# OpenBook_Schematic_v39.net
KiCad netlist of a schematic drawn in EAGLE
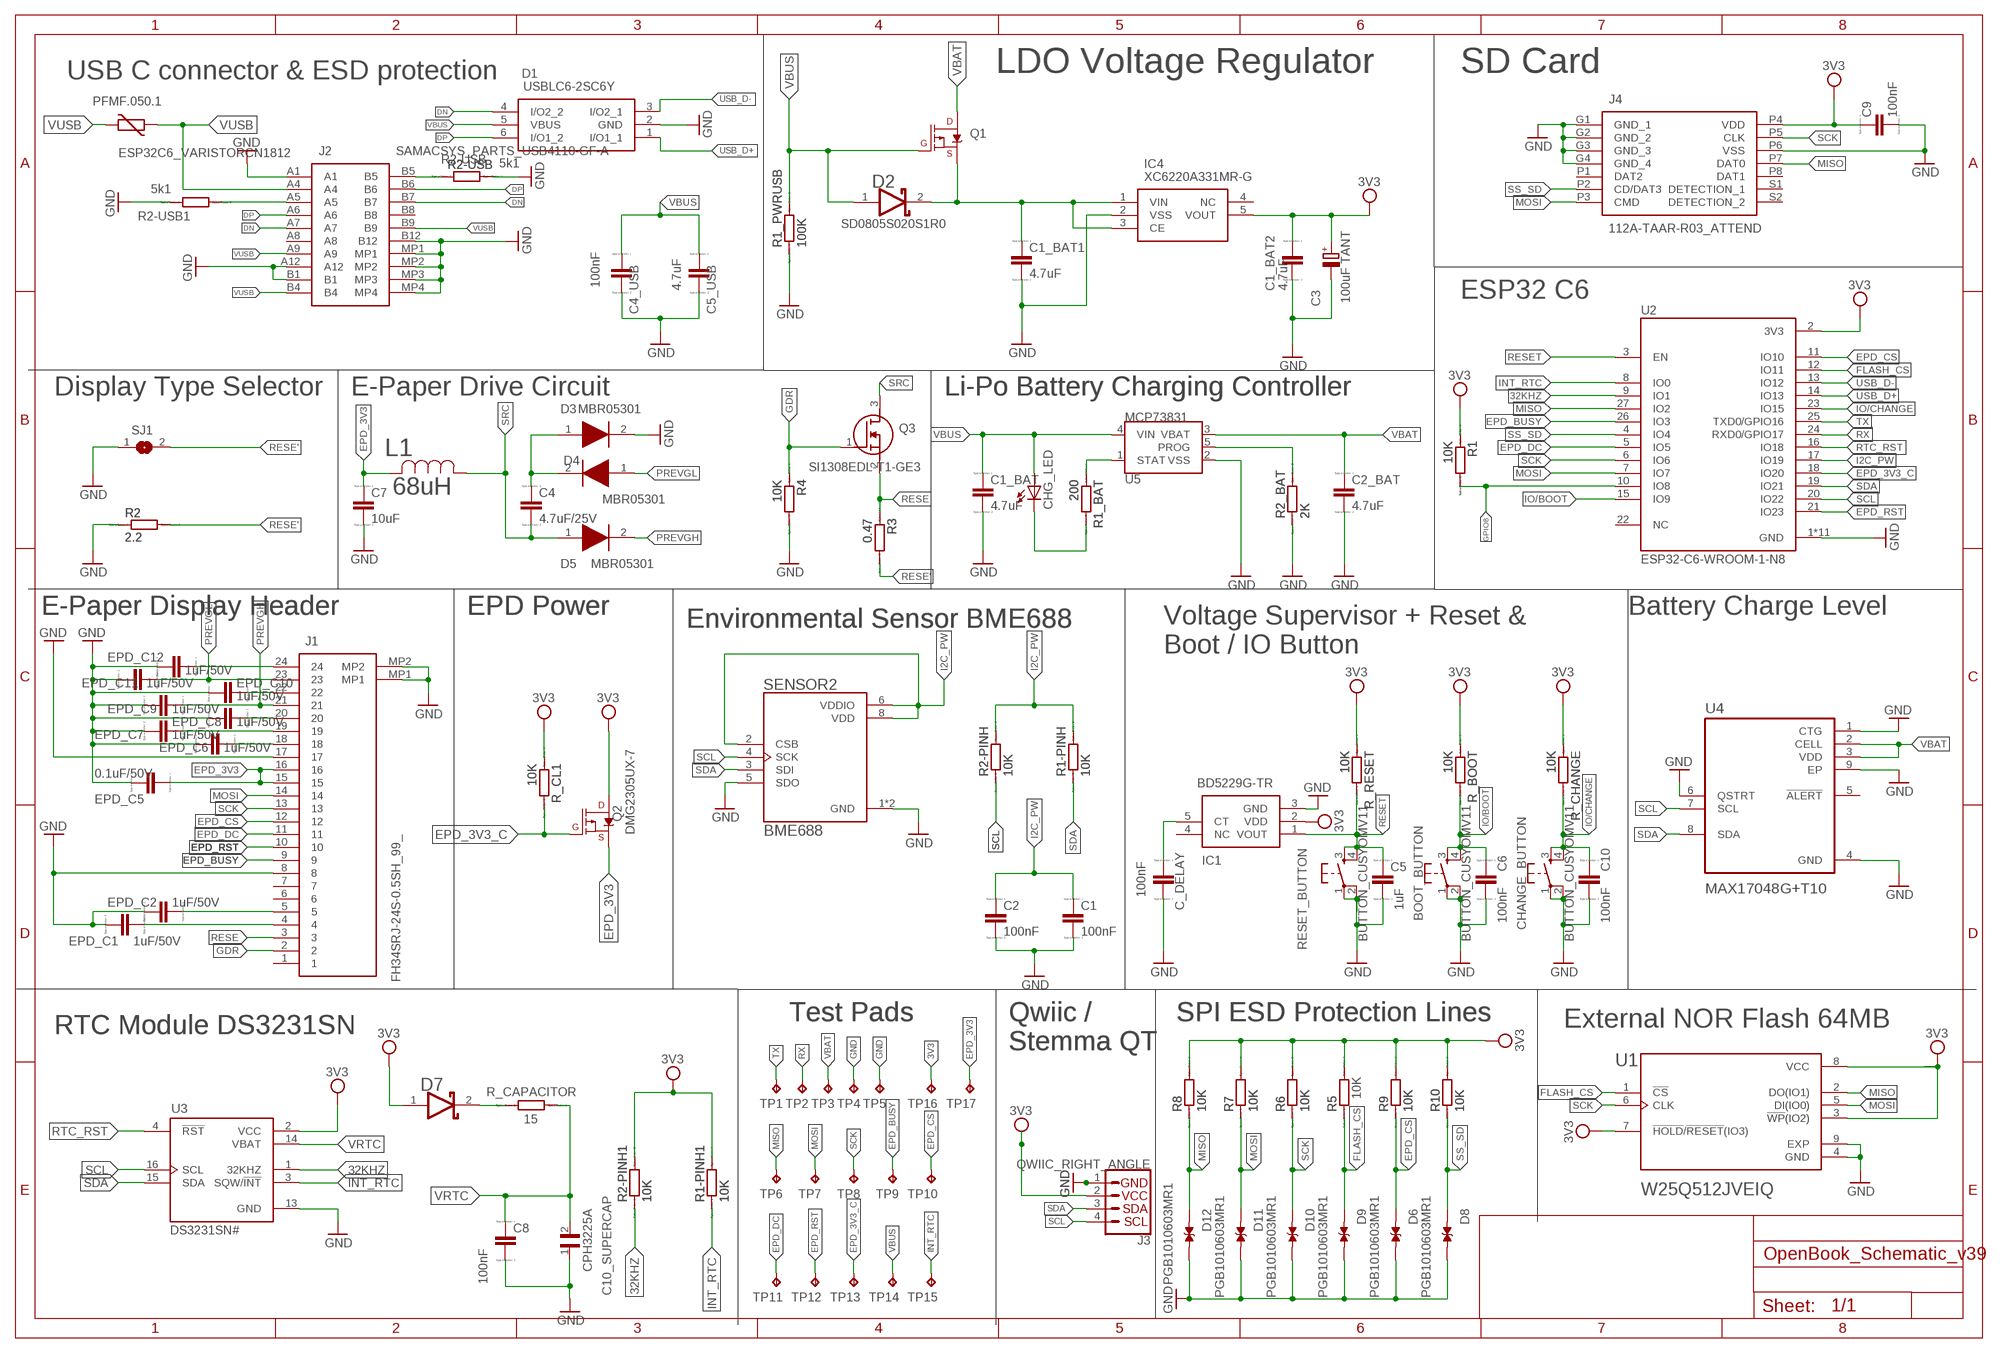
[diagram p0: schematic, sheet 1]

(export (version "E")
  (design (tool "Eeschema 10.0.6"))
  (components
    (comp (ref "BOOT_BUTTON")
      (value "BUTTON_CUSYOMV11")
      (footprint "eagle-import:MYBUTTON")
      (libsource (lib "eagle-import") (part "BUTTON_CUSYOMV11"))
    )
    (comp (ref "C1")
      (value "100nF")
      (footprint "eagle-import:EAGLE-LTSPICE_C0402")
      (libsource (lib "eagle-import") (part "EAGLE-LTSPICE_C"))
    )
    (comp (ref "C1_BAT")
      (value "4.7uF")
      (footprint "eagle-import:EAGLE-LTSPICE_C0402")
      (libsource (lib "eagle-import") (part "EAGLE-LTSPICE_C"))
    )
    (comp (ref "C1_BAT1")
      (value "4.7uF")
      (footprint "eagle-import:EAGLE-LTSPICE_C0402")
      (libsource (lib "eagle-import") (part "EAGLE-LTSPICE_C"))
    )
    (comp (ref "C1_BAT2")
      (value "4.7uF")
      (footprint "eagle-import:EAGLE-LTSPICE_C0402")
      (libsource (lib "eagle-import") (part "EAGLE-LTSPICE_C"))
    )
    (comp (ref "C2")
      (value "100nF")
      (footprint "eagle-import:EAGLE-LTSPICE_C0402")
      (libsource (lib "eagle-import") (part "EAGLE-LTSPICE_C"))
    )
    (comp (ref "C2_BAT")
      (value "4.7uF")
      (footprint "eagle-import:EAGLE-LTSPICE_C0402")
      (libsource (lib "eagle-import") (part "EAGLE-LTSPICE_C"))
    )
    (comp (ref "C3")
      (value "100uF TANT")
      (footprint "eagle-import:RCL_CT3528")
      (libsource (lib "eagle-import") (part "RCL_CPOL-EUCT3528"))
    )
    (comp (ref "C4")
      (value "4.7uF/25V")
      (footprint "eagle-import:EAGLE-LTSPICE_C0402")
      (libsource (lib "eagle-import") (part "EAGLE-LTSPICE_C"))
    )
    (comp (ref "C4_USB")
      (value "100nF")
      (footprint "eagle-import:EAGLE-LTSPICE_C0402")
      (libsource (lib "eagle-import") (part "EAGLE-LTSPICE_C"))
    )
    (comp (ref "C5")
      (value "1uF")
      (footprint "eagle-import:EAGLE-LTSPICE_C0402")
      (libsource (lib "eagle-import") (part "EAGLE-LTSPICE_C"))
    )
    (comp (ref "C5_USB")
      (value "4.7uF")
      (footprint "eagle-import:EAGLE-LTSPICE_C0402")
      (libsource (lib "eagle-import") (part "EAGLE-LTSPICE_C"))
    )
    (comp (ref "C6")
      (value "100nF")
      (footprint "eagle-import:EAGLE-LTSPICE_C0402")
      (libsource (lib "eagle-import") (part "EAGLE-LTSPICE_C"))
    )
    (comp (ref "C7")
      (value "10uF")
      (footprint "eagle-import:EAGLE-LTSPICE_C0402")
      (libsource (lib "eagle-import") (part "EAGLE-LTSPICE_C"))
    )
    (comp (ref "C8")
      (value "100nF")
      (footprint "eagle-import:EAGLE-LTSPICE_C0402")
      (libsource (lib "eagle-import") (part "EAGLE-LTSPICE_C"))
    )
    (comp (ref "C9")
      (value "100nF")
      (footprint "eagle-import:EAGLE-LTSPICE_C0402")
      (libsource (lib "eagle-import") (part "EAGLE-LTSPICE_C"))
    )
    (comp (ref "C10")
      (value "100nF")
      (footprint "eagle-import:EAGLE-LTSPICE_C0402")
      (libsource (lib "eagle-import") (part "EAGLE-LTSPICE_C"))
    )
    (comp (ref "C10_SUPERCAP")
      (value "CPH3225A")
      (footprint "eagle-import:CAPCP3225X100N")
      (fields (field (name "MF") "Seiko Instruments"))
      (libsource (lib "eagle-import") (part "CPH3225A"))
    )
    (comp (ref "CHANGE_BUTTON")
      (value "BUTTON_CUSYOMV11")
      (footprint "eagle-import:MYBUTTON")
      (libsource (lib "eagle-import") (part "BUTTON_CUSYOMV11"))
    )
    (comp (ref "CHG_LED")
      (value "ADAFRUIT_LEDCHIP-LED0603")
      (footprint "eagle-import:ADAFRUIT_CHIP-LED0603")
      (libsource (lib "eagle-import") (part "ADAFRUIT_LEDCHIP-LED0603"))
    )
    (comp (ref "C_DELAY")
      (value "100nF")
      (footprint "eagle-import:EAGLE-LTSPICE_C0402")
      (libsource (lib "eagle-import") (part "EAGLE-LTSPICE_C"))
    )
    (comp (ref "D1")
      (value "USBLC6-2SC6Y")
      (footprint "eagle-import:SOT95P280X145-6N")
      (fields (field (name "MF") "STMicroelectronics"))
      (libsource (lib "eagle-import") (part "USBLC6-2SC6Y"))
    )
    (comp (ref "D2")
      (value "SD0805S020S1R0")
      (footprint "eagle-import:ESP32_WROVER_AVX---SD0805S020S1R0_AVX_SD0805S020S1R0_0")
      (fields (field (name "MINE") "SD0805S020S1R0"))
      (libsource (lib "eagle-import") (part "ESP32_WROVER_AVX---SD0805S020S1R0_AVX_SD0805S020S1R0_0_0"))
    )
    (comp (ref "D3")
      (value "MBR05301")
      (footprint "eagle-import:SOD3716X135N")
      (libsource (lib "eagle-import") (part "MBR05301"))
    )
    (comp (ref "D4")
      (value "MBR05301")
      (footprint "eagle-import:SOD3716X135N")
      (libsource (lib "eagle-import") (part "MBR05301"))
    )
    (comp (ref "D5")
      (value "MBR05301")
      (footprint "eagle-import:SOD3716X135N")
      (libsource (lib "eagle-import") (part "MBR05301"))
    )
    (comp (ref "D6")
      (value "PGB1010603MR1")
      (footprint "eagle-import:DIOC1608X36N")
      (libsource (lib "eagle-import") (part "PGB1010603MR1"))
    )
    (comp (ref "D7")
      (value "SD0805S020S1R0")
      (footprint "eagle-import:ESP32_WROVER_AVX---SD0805S020S1R0_AVX_SD0805S020S1R0_0")
      (libsource (lib "eagle-import") (part "ESP32_WROVER_AVX---SD0805S020S1R0_AVX_SD0805S020S1R0_0_0"))
    )
    (comp (ref "D8")
      (value "PGB1010603MR1")
      (footprint "eagle-import:DIOC1608X36N")
      (libsource (lib "eagle-import") (part "PGB1010603MR1"))
    )
    (comp (ref "D9")
      (value "PGB1010603MR1")
      (footprint "eagle-import:DIOC1608X36N")
      (libsource (lib "eagle-import") (part "PGB1010603MR1"))
    )
    (comp (ref "D10")
      (value "PGB1010603MR1")
      (footprint "eagle-import:DIOC1608X36N")
      (libsource (lib "eagle-import") (part "PGB1010603MR1"))
    )
    (comp (ref "D11")
      (value "PGB1010603MR1")
      (footprint "eagle-import:DIOC1608X36N")
      (libsource (lib "eagle-import") (part "PGB1010603MR1"))
    )
    (comp (ref "D12")
      (value "PGB1010603MR1")
      (footprint "eagle-import:DIOC1608X36N")
      (libsource (lib "eagle-import") (part "PGB1010603MR1"))
    )
    (comp (ref "EPD_C1")
      (value "1uF/50V")
      (footprint "eagle-import:EAGLE-LTSPICE_C0402")
      (libsource (lib "eagle-import") (part "EAGLE-LTSPICE_C"))
    )
    (comp (ref "EPD_C2")
      (value "1uF/50V")
      (footprint "eagle-import:EAGLE-LTSPICE_C0402")
      (libsource (lib "eagle-import") (part "EAGLE-LTSPICE_C"))
    )
    (comp (ref "EPD_C5")
      (value "0.1uF/50V")
      (footprint "eagle-import:EAGLE-LTSPICE_C0402")
      (libsource (lib "eagle-import") (part "EAGLE-LTSPICE_C"))
    )
    (comp (ref "EPD_C6")
      (value "1uF/50V")
      (footprint "eagle-import:EAGLE-LTSPICE_C0402")
      (libsource (lib "eagle-import") (part "EAGLE-LTSPICE_C"))
    )
    (comp (ref "EPD_C7")
      (value "1uF/50V")
      (footprint "eagle-import:EAGLE-LTSPICE_C0402")
      (libsource (lib "eagle-import") (part "EAGLE-LTSPICE_C"))
    )
    (comp (ref "EPD_C8")
      (value "1uF/50V")
      (footprint "eagle-import:EAGLE-LTSPICE_C0402")
      (libsource (lib "eagle-import") (part "EAGLE-LTSPICE_C"))
    )
    (comp (ref "EPD_C9")
      (value "1uF/50V")
      (footprint "eagle-import:EAGLE-LTSPICE_C0402")
      (libsource (lib "eagle-import") (part "EAGLE-LTSPICE_C"))
    )
    (comp (ref "EPD_C10")
      (value "1uF/50V")
      (footprint "eagle-import:EAGLE-LTSPICE_C0402")
      (libsource (lib "eagle-import") (part "EAGLE-LTSPICE_C"))
    )
    (comp (ref "EPD_C11")
      (value "1uF/50V")
      (footprint "eagle-import:EAGLE-LTSPICE_C0402")
      (libsource (lib "eagle-import") (part "EAGLE-LTSPICE_C"))
    )
    (comp (ref "EPD_C12")
      (value "1uF/50V")
      (footprint "eagle-import:EAGLE-LTSPICE_C0402")
      (libsource (lib "eagle-import") (part "EAGLE-LTSPICE_C"))
    )
    (comp (ref "IC1")
      (value "BD5229G-TR")
      (footprint "eagle-import:SOT95P280X125-5N")
      (fields (field (name "MOUSER_PART_NUMBER") "755-BD5229G-TR"))
      (libsource (lib "eagle-import") (part "BD5229G-TR"))
    )
    (comp (ref "IC4")
      (value "XC6220A331MR-G")
      (footprint "eagle-import:SOT95P280X120-5N")
      (fields (field (name "MOUSER_PART_NUMBER") "865-XC6220A331MR-G"))
      (libsource (lib "eagle-import") (part "XC6220A331MR-G"))
    )
    (comp (ref "J1")
      (value "FH34SRJ-24S-0.5SH_99_")
      (footprint "eagle-import:FH34SRJ24S05SH99")
      (fields
        (field (name "MANUFACTURER_PART_NUMBER") "FH34SRJ-24S-0.5SH(99)")
        (field (name "MOUSER_PART_NUMBER") "798-FH34SRJ24S05SH99")
      )
      (libsource (lib "eagle-import") (part "FH34SRJ-24S-0.5SH_99_"))
    )
    (comp (ref "J2")
      (value "SAMACSYS_PARTS_USB4110-GF-A")
      (footprint "eagle-import:SAMACSYS_PARTS_USB4110GFA")
      (fields
        (field (name "MANUFACTURER_PART_NUMBER") "USB4110-GF-A")
        (field (name "MOUSER_PART_NUMBER") "640-USB4110-GF-A")
      )
      (libsource (lib "eagle-import") (part "SAMACSYS_PARTS_USB4110-GF-A"))
    )
    (comp (ref "J3")
      (value "QWIIC_RIGHT_ANGLE")
      (footprint "eagle-import:JST04_1MM_RA")
      (libsource (lib "eagle-import") (part "QWIIC_CONNECTORJS-1MM"))
    )
    (comp (ref "J4")
      (value "112A-TAAR-R03_ATTEND")
      (footprint "eagle-import:112ATAARR03ATTEND")
      (fields (field (name "MANUFACTURER_PART_NUMBER") "112A-TAAR-R03 ATTEND"))
      (libsource (lib "eagle-import") (part "112A-TAAR-R03_ATTEND"))
    )
    (comp (ref "L1")
      (value "68uH")
      (footprint "eagle-import:IND_4828-WE-TPC_WRE")
      (fields
        (field (name "MANUFACTURER_PART_NUMBER") "744043680")
        (field (name "COPYRIGHT") "Copyright (C) 2024 Ultra Librarian. All rights reserved.")
      )
      (libsource (lib "eagle-import") (part "744043680IND_4828-WE-TPC_WRE"))
    )
    (comp (ref "PFMF.050.1")
      (value "ESP32C6_VARISTORCN1812")
      (footprint "eagle-import:ESP32C6_VARISTOR_CT_CN1812")
      (libsource (lib "eagle-import") (part "ESP32C6_VARISTORCN1812"))
    )
    (comp (ref "Q1")
      (value "20V/4.2A/52mΩ/1.4W")
      (footprint "eagle-import:ESP32_WROVER_SPARKFUN-DISCRETESEMI_SOT23-3")
      (libsource (lib "eagle-import") (part "ESP32_WROVER_SPARKFUN-DISCRETESEMI_MOSFET_PCH"))
    )
    (comp (ref "Q2")
      (value "20V/4.2A/52mΩ/1.4W")
      (footprint "eagle-import:ESP32_WROVER_SPARKFUN-DISCRETESEMI_SOT23-3")
      (fields (field (name "MINE") "DMG2305UX-7"))
      (libsource (lib "eagle-import") (part "ESP32_WROVER_SPARKFUN-DISCRETESEMI_MOSFET_PCH"))
    )
    (comp (ref "Q3")
      (value "SI1308EDL-T1-GE3")
      (footprint "eagle-import:SOT65P210X110-3N")
      (fields (field (name "MF") "Vishay Siliconix"))
      (libsource (lib "eagle-import") (part "SI1308EDL-T1-GE3"))
    )
    (comp (ref "R1")
      (value "10K")
      (footprint "eagle-import:ESP32_WROVER_EAGLE-LTSPICE_R0402")
      (libsource (lib "eagle-import") (part "ESP32_WROVER_EAGLE-LTSPICE_R"))
    )
    (comp (ref "R1-PINH")
      (value "10K")
      (footprint "eagle-import:ESP32_WROVER_EAGLE-LTSPICE_R0402")
      (libsource (lib "eagle-import") (part "ESP32_WROVER_EAGLE-LTSPICE_R"))
    )
    (comp (ref "R1-PINH1")
      (value "10K")
      (footprint "eagle-import:ESP32_WROVER_EAGLE-LTSPICE_R0402")
      (libsource (lib "eagle-import") (part "ESP32_WROVER_EAGLE-LTSPICE_R"))
    )
    (comp (ref "R1_BAT")
      (value "200")
      (footprint "eagle-import:ESP32_WROVER_EAGLE-LTSPICE_R0402")
      (libsource (lib "eagle-import") (part "ESP32_WROVER_EAGLE-LTSPICE_R"))
    )
    (comp (ref "R1_PWRUSB")
      (value "100K")
      (footprint "eagle-import:ESP32_WROVER_EAGLE-LTSPICE_R0402")
      (libsource (lib "eagle-import") (part "ESP32_WROVER_EAGLE-LTSPICE_R"))
    )
    (comp (ref "R2")
      (value "2.2")
      (footprint "eagle-import:ESP32_WROVER_EAGLE-LTSPICE_R0402")
      (libsource (lib "eagle-import") (part "ESP32_WROVER_EAGLE-LTSPICE_R"))
    )
    (comp (ref "R2-PINH")
      (value "10K")
      (footprint "eagle-import:ESP32_WROVER_EAGLE-LTSPICE_R0402")
      (libsource (lib "eagle-import") (part "ESP32_WROVER_EAGLE-LTSPICE_R"))
    )
    (comp (ref "R2-PINH1")
      (value "10K")
      (footprint "eagle-import:ESP32_WROVER_EAGLE-LTSPICE_R0402")
      (libsource (lib "eagle-import") (part "ESP32_WROVER_EAGLE-LTSPICE_R"))
    )
    (comp (ref "R2-USB")
      (value "5k1")
      (footprint "eagle-import:ESP32_WROVER_EAGLE-LTSPICE_R0402")
      (libsource (lib "eagle-import") (part "ESP32_WROVER_EAGLE-LTSPICE_R"))
    )
    (comp (ref "R2-USB1")
      (value "5k1")
      (footprint "eagle-import:ESP32_WROVER_EAGLE-LTSPICE_R0402")
      (libsource (lib "eagle-import") (part "ESP32_WROVER_EAGLE-LTSPICE_R"))
    )
    (comp (ref "R2_BAT")
      (value "2K")
      (footprint "eagle-import:ESP32_WROVER_EAGLE-LTSPICE_R0402")
      (libsource (lib "eagle-import") (part "ESP32_WROVER_EAGLE-LTSPICE_R"))
    )
    (comp (ref "R3")
      (value "0.47")
      (footprint "eagle-import:ESP32_WROVER_EAGLE-LTSPICE_R0402")
      (libsource (lib "eagle-import") (part "ESP32_WROVER_EAGLE-LTSPICE_R"))
    )
    (comp (ref "R4")
      (value "10K")
      (footprint "eagle-import:ESP32_WROVER_EAGLE-LTSPICE_R0402")
      (libsource (lib "eagle-import") (part "ESP32_WROVER_EAGLE-LTSPICE_R"))
    )
    (comp (ref "R5")
      (value "10K")
      (footprint "eagle-import:ESP32_WROVER_EAGLE-LTSPICE_R0402")
      (libsource (lib "eagle-import") (part "ESP32_WROVER_EAGLE-LTSPICE_R"))
    )
    (comp (ref "R6")
      (value "10K")
      (footprint "eagle-import:ESP32_WROVER_EAGLE-LTSPICE_R0402")
      (libsource (lib "eagle-import") (part "ESP32_WROVER_EAGLE-LTSPICE_R"))
    )
    (comp (ref "R7")
      (value "10K")
      (footprint "eagle-import:ESP32_WROVER_EAGLE-LTSPICE_R0402")
      (libsource (lib "eagle-import") (part "ESP32_WROVER_EAGLE-LTSPICE_R"))
    )
    (comp (ref "R8")
      (value "10K")
      (footprint "eagle-import:ESP32_WROVER_EAGLE-LTSPICE_R0402")
      (libsource (lib "eagle-import") (part "ESP32_WROVER_EAGLE-LTSPICE_R"))
    )
    (comp (ref "R9")
      (value "10K")
      (footprint "eagle-import:ESP32_WROVER_EAGLE-LTSPICE_R0402")
      (libsource (lib "eagle-import") (part "ESP32_WROVER_EAGLE-LTSPICE_R"))
    )
    (comp (ref "R10")
      (value "10K")
      (footprint "eagle-import:ESP32_WROVER_EAGLE-LTSPICE_R0402")
      (libsource (lib "eagle-import") (part "ESP32_WROVER_EAGLE-LTSPICE_R"))
    )
    (comp (ref "RESET_BUTTON")
      (value "BUTTON_CUSYOMV11")
      (footprint "eagle-import:MYBUTTON")
      (libsource (lib "eagle-import") (part "BUTTON_CUSYOMV11"))
    )
    (comp (ref "R_BOOT")
      (value "10K")
      (footprint "eagle-import:ESP32_WROVER_EAGLE-LTSPICE_R0402")
      (libsource (lib "eagle-import") (part "ESP32_WROVER_EAGLE-LTSPICE_R"))
    )
    (comp (ref "R_CAPACITOR")
      (value "15")
      (footprint "eagle-import:ESP32_WROVER_EAGLE-LTSPICE_R0402")
      (libsource (lib "eagle-import") (part "ESP32_WROVER_EAGLE-LTSPICE_R"))
    )
    (comp (ref "R_CHANGE")
      (value "10K")
      (footprint "eagle-import:ESP32_WROVER_EAGLE-LTSPICE_R0402")
      (libsource (lib "eagle-import") (part "ESP32_WROVER_EAGLE-LTSPICE_R"))
    )
    (comp (ref "R_CL1")
      (value "10K")
      (footprint "eagle-import:ESP32_WROVER_EAGLE-LTSPICE_R0402")
      (libsource (lib "eagle-import") (part "ESP32_WROVER_EAGLE-LTSPICE_R"))
    )
    (comp (ref "R_RESET")
      (value "10K")
      (footprint "eagle-import:ESP32_WROVER_EAGLE-LTSPICE_R0402")
      (libsource (lib "eagle-import") (part "ESP32_WROVER_EAGLE-LTSPICE_R"))
    )
    (comp (ref "SENSOR2")
      (value "BME688")
      (footprint "eagle-import:ESP32_WROVER_BME680_PSON80P300X300X100-8N")
      (fields (field (name "MF") "Bosch Sensortec") (field (name "MP") "BME680"))
      (libsource (lib "eagle-import") (part "ESP32_WROVER_BME680_BME680"))
    )
    (comp (ref "SJ1") (value "SJ") (footprint "eagle-import:SJ") (libsource (lib "eagle-import") (part "SJ")))
    (comp (ref "TP1")
      (value "TPTP20R")
      (footprint "eagle-import:TP20R")
      (libsource (lib "eagle-import") (part "TPTP20R"))
    )
    (comp (ref "TP2")
      (value "TPTP20R")
      (footprint "eagle-import:TP20R")
      (libsource (lib "eagle-import") (part "TPTP20R"))
    )
    (comp (ref "TP3")
      (value "TPTP20R")
      (footprint "eagle-import:TP20R")
      (libsource (lib "eagle-import") (part "TPTP20R"))
    )
    (comp (ref "TP4")
      (value "TPTP20R")
      (footprint "eagle-import:TP20R")
      (libsource (lib "eagle-import") (part "TPTP20R"))
    )
    (comp (ref "TP5")
      (value "TPTP20R")
      (footprint "eagle-import:TP20R")
      (libsource (lib "eagle-import") (part "TPTP20R"))
    )
    (comp (ref "TP6")
      (value "TPTP20R")
      (footprint "eagle-import:TP20R")
      (libsource (lib "eagle-import") (part "TPTP20R"))
    )
    (comp (ref "TP7")
      (value "TPTP20R")
      (footprint "eagle-import:TP20R")
      (libsource (lib "eagle-import") (part "TPTP20R"))
    )
    (comp (ref "TP8")
      (value "TPTP20R")
      (footprint "eagle-import:TP20R")
      (libsource (lib "eagle-import") (part "TPTP20R"))
    )
    (comp (ref "TP9")
      (value "TPTP20R")
      (footprint "eagle-import:TP20R")
      (libsource (lib "eagle-import") (part "TPTP20R"))
    )
    (comp (ref "TP10")
      (value "TPTP20R")
      (footprint "eagle-import:TP20R")
      (libsource (lib "eagle-import") (part "TPTP20R"))
    )
    (comp (ref "TP11")
      (value "TPTP20R")
      (footprint "eagle-import:TP20R")
      (libsource (lib "eagle-import") (part "TPTP20R"))
    )
    (comp (ref "TP12")
      (value "TPTP20R")
      (footprint "eagle-import:TP20R")
      (libsource (lib "eagle-import") (part "TPTP20R"))
    )
    (comp (ref "TP13")
      (value "TPTP20R")
      (footprint "eagle-import:TP20R")
      (libsource (lib "eagle-import") (part "TPTP20R"))
    )
    (comp (ref "TP14")
      (value "TPTP20R")
      (footprint "eagle-import:TP20R")
      (libsource (lib "eagle-import") (part "TPTP20R"))
    )
    (comp (ref "TP15")
      (value "TPTP20R")
      (footprint "eagle-import:TP20R")
      (libsource (lib "eagle-import") (part "TPTP20R"))
    )
    (comp (ref "TP16")
      (value "TPTP20R")
      (footprint "eagle-import:TP20R")
      (libsource (lib "eagle-import") (part "TPTP20R"))
    )
    (comp (ref "TP17")
      (value "TPTP20R")
      (footprint "eagle-import:TP20R")
      (libsource (lib "eagle-import") (part "TPTP20R"))
    )
    (comp (ref "U1")
      (value "W25Q512JVEIQ")
      (footprint "eagle-import:SON127P600X800X80-9N")
      (fields (field (name "MF") "Winbond Electronics"))
      (libsource (lib "eagle-import") (part "W25Q512JVEIQ"))
    )
    (comp (ref "U2")
      (value "ESP32-C6-WROOM-1-N8")
      (footprint "eagle-import:XCVR_ESP32-C6-WROOM-1-N8")
      (fields (field (name "MF") "Espressif Systems"))
      (libsource (lib "eagle-import") (part "ESP32-C6-WROOM-1-N8"))
    )
    (comp (ref "U3")
      (value "DS3231SN#")
      (footprint "eagle-import:SOIC127P1032X265-16N")
      (fields (field (name "MF") "Analog Devices"))
      (libsource (lib "eagle-import") (part "DS3231SN#"))
    )
    (comp (ref "U4")
      (value "MAX17048G+T10")
      (footprint "eagle-import:SON50P200X200X80-9N")
      (fields (field (name "MF") "Analog Devices"))
      (libsource (lib "eagle-import") (part "MAX17048G+T10"))
    )
    (comp (ref "U5")
      (value "MCP73831")
      (footprint "eagle-import:ESP32_WROVER_SPARKFUN-IC-POWER_SOT23-5")
      (libsource (lib "eagle-import") (part "ESP32_WROVER_SPARKFUN-IC-POWER_MCP73831"))
    )
  )
  (nets
    (net (code "1") (name "3V3") (class "Default")
      (node (ref "C1_BAT2") (pin "1") (pinfunction "1_1") (pintype "passive"))
      (node (ref "C3") (pin "+") (pinfunction "+_+") (pintype "passive"))
      (node (ref "C9") (pin "1") (pinfunction "1_1") (pintype "passive"))
      (node (ref "D7") (pin "1") (pinfunction "ANODE_1") (pintype "bidirectional"))
      (node (ref "IC1") (pin "2") (pinfunction "VDD_2") (pintype "bidirectional"))
      (node (ref "IC4") (pin "5") (pinfunction "VOUT_5") (pintype "bidirectional"))
      (node (ref "J3") (pin "2") (pinfunction "2_2") (pintype "power_in"))
      (node (ref "J4") (pin "P4") (pinfunction "VDD_P4") (pintype "bidirectional"))
      (node (ref "Q2") (pin "1") (pinfunction "D_1") (pintype "bidirectional"))
      (node (ref "R1") (pin "1") (pinfunction "1_1") (pintype "passive"))
      (node (ref "R1-PINH1") (pin "2") (pinfunction "2_2") (pintype "passive"))
      (node (ref "R10") (pin "2") (pinfunction "2_2") (pintype "passive"))
      (node (ref "R2-PINH1") (pin "2") (pinfunction "2_2") (pintype "passive"))
      (node (ref "R5") (pin "2") (pinfunction "2_2") (pintype "passive"))
      (node (ref "R6") (pin "2") (pinfunction "2_2") (pintype "passive"))
      (node (ref "R7") (pin "2") (pinfunction "2_2") (pintype "passive"))
      (node (ref "R8") (pin "2") (pinfunction "2_2") (pintype "passive"))
      (node (ref "R9") (pin "2") (pinfunction "2_2") (pintype "passive"))
      (node (ref "R_BOOT") (pin "1") (pinfunction "1_1") (pintype "passive"))
      (node (ref "R_CHANGE") (pin "1") (pinfunction "1_1") (pintype "passive"))
      (node (ref "R_CL1") (pin "1") (pinfunction "1_1") (pintype "passive"))
      (node (ref "R_RESET") (pin "1") (pinfunction "1_1") (pintype "passive"))
      (node (ref "TP16") (pin "TP") (pinfunction "TP_TP") (pintype "input"))
      (node (ref "U1") (pin "3") (pinfunction "~{WP}(IO2)_3") (pintype "bidirectional"))
      (node (ref "U1") (pin "7") (pinfunction "~{HOLD}/~{RESET}(IO3)_7") (pintype "bidirectional"))
      (node (ref "U1") (pin "8") (pinfunction "VCC_8") (pintype "power_in"))
      (node (ref "U2") (pin "2") (pinfunction "3V3_2") (pintype "power_in"))
      (node (ref "U3") (pin "2") (pinfunction "VCC_2") (pintype "power_in"))
    )
    (net (code "2") (name "32KHZ") (class "Default")
      (node (ref "R2-PINH1") (pin "1") (pinfunction "1_1") (pintype "passive"))
      (node (ref "U2") (pin "9") (pinfunction "IO1_9") (pintype "bidirectional"))
      (node (ref "U3") (pin "1") (pinfunction "32KHZ_1") (pintype "output"))
    )
    (net (code "3") (name "DN") (class "Default")
      (node (ref "D1") (pin "4") (pinfunction "I/O2_2_4") (pintype "bidirectional"))
      (node (ref "J2") (pin "A7") (pinfunction "A7_A7") (pintype "bidirectional"))
      (node (ref "J2") (pin "B7") (pinfunction "B7_B7") (pintype "bidirectional"))
    )
    (net (code "4") (name "DP") (class "Default")
      (node (ref "D1") (pin "6") (pinfunction "I/O1_2_6") (pintype "bidirectional"))
      (node (ref "J2") (pin "A6") (pinfunction "A6_A6") (pintype "bidirectional"))
      (node (ref "J2") (pin "B6") (pinfunction "B6_B6") (pintype "bidirectional"))
    )
    (net (code "5") (name "EPD_3V3") (class "Default")
      (node (ref "C7") (pin "1") (pinfunction "1_1") (pintype "passive"))
      (node (ref "EPD_C5") (pin "1") (pinfunction "1_1") (pintype "passive"))
      (node (ref "J1") (pin "15") (pinfunction "15_15") (pintype "bidirectional"))
      (node (ref "J1") (pin "16") (pinfunction "16_16") (pintype "bidirectional"))
      (node (ref "L1") (pin "2") (pinfunction "2_2") (pintype "passive"))
      (node (ref "Q2") (pin "3") (pinfunction "S_3") (pintype "bidirectional"))
      (node (ref "TP17") (pin "TP") (pinfunction "TP_TP") (pintype "input"))
    )
    (net (code "6") (name "EPD_3V3_C") (class "Default")
      (node (ref "Q2") (pin "2") (pinfunction "G_2") (pintype "bidirectional"))
      (node (ref "R_CL1") (pin "2") (pinfunction "2_2") (pintype "passive"))
      (node (ref "TP13") (pin "TP") (pinfunction "TP_TP") (pintype "input"))
      (node (ref "U2") (pin "18") (pinfunction "IO20_18") (pintype "bidirectional"))
    )
    (net (code "7") (name "EPD_BUSY") (class "Default")
      (node (ref "J1") (pin "9") (pinfunction "9_9") (pintype "bidirectional"))
      (node (ref "TP9") (pin "TP") (pinfunction "TP_TP") (pintype "input"))
      (node (ref "U2") (pin "26") (pinfunction "IO3_26") (pintype "bidirectional"))
    )
    (net (code "8") (name "EPD_CS") (class "Default")
      (node (ref "D6") (pin "1") (pinfunction "1_1") (pintype "passive"))
      (node (ref "J1") (pin "12") (pinfunction "12_12") (pintype "bidirectional"))
      (node (ref "R9") (pin "1") (pinfunction "1_1") (pintype "passive"))
      (node (ref "TP10") (pin "TP") (pinfunction "TP_TP") (pintype "input"))
      (node (ref "U2") (pin "11") (pinfunction "IO10_11") (pintype "bidirectional"))
    )
    (net (code "9") (name "EPD_DC") (class "Default")
      (node (ref "J1") (pin "11") (pinfunction "11_11") (pintype "bidirectional"))
      (node (ref "TP11") (pin "TP") (pinfunction "TP_TP") (pintype "input"))
      (node (ref "U2") (pin "5") (pinfunction "IO5_5") (pintype "bidirectional"))
    )
    (net (code "10") (name "EPD_RST") (class "Default")
      (node (ref "J1") (pin "10") (pinfunction "10_10") (pintype "bidirectional"))
      (node (ref "TP12") (pin "TP") (pinfunction "TP_TP") (pintype "input"))
      (node (ref "U2") (pin "21") (pinfunction "IO23_21") (pintype "bidirectional"))
    )
    (net (code "11") (name "FLASH_CS") (class "Default")
      (node (ref "D9") (pin "1") (pinfunction "1_1") (pintype "passive"))
      (node (ref "R5") (pin "1") (pinfunction "1_1") (pintype "passive"))
      (node (ref "U1") (pin "1") (pinfunction "~{CS}_1") (pintype "input"))
      (node (ref "U2") (pin "12") (pinfunction "IO11_12") (pintype "bidirectional"))
    )
    (net (code "12") (name "GDR") (class "Default")
      (node (ref "J1") (pin "2") (pinfunction "2_2") (pintype "bidirectional"))
      (node (ref "Q3") (pin "1") (pinfunction "G_1") (pintype "bidirectional"))
      (node (ref "R4") (pin "1") (pinfunction "1_1") (pintype "passive"))
    )
    (net (code "13") (name "GND") (class "Default")
      (node (ref "BOOT_BUTTON") (pin "1") (pinfunction "1_1") (pintype "passive"))
      (node (ref "BOOT_BUTTON") (pin "2") (pinfunction "2_2") (pintype "passive"))
      (node (ref "C1") (pin "2") (pinfunction "2_2") (pintype "passive"))
      (node (ref "C10") (pin "2") (pinfunction "2_2") (pintype "passive"))
      (node (ref "C10_SUPERCAP") (pin "1") (pinfunction "1_1") (pintype "passive"))
      (node (ref "C1_BAT") (pin "2") (pinfunction "2_2") (pintype "passive"))
      (node (ref "C1_BAT1") (pin "2") (pinfunction "2_2") (pintype "passive"))
      (node (ref "C1_BAT2") (pin "2") (pinfunction "2_2") (pintype "passive"))
      (node (ref "C2") (pin "2") (pinfunction "2_2") (pintype "passive"))
      (node (ref "C2_BAT") (pin "2") (pinfunction "2_2") (pintype "passive"))
      (node (ref "C3") (pin "-") (pinfunction "-_-") (pintype "passive"))
      (node (ref "C4_USB") (pin "2") (pinfunction "2_2") (pintype "passive"))
      (node (ref "C5") (pin "2") (pinfunction "2_2") (pintype "passive"))
      (node (ref "C5_USB") (pin "2") (pinfunction "2_2") (pintype "passive"))
      (node (ref "C6") (pin "2") (pinfunction "2_2") (pintype "passive"))
      (node (ref "C7") (pin "2") (pinfunction "2_2") (pintype "passive"))
      (node (ref "C8") (pin "2") (pinfunction "2_2") (pintype "passive"))
      (node (ref "C9") (pin "2") (pinfunction "2_2") (pintype "passive"))
      (node (ref "CHANGE_BUTTON") (pin "1") (pinfunction "1_1") (pintype "passive"))
      (node (ref "CHANGE_BUTTON") (pin "2") (pinfunction "2_2") (pintype "passive"))
      (node (ref "C_DELAY") (pin "2") (pinfunction "2_2") (pintype "passive"))
      (node (ref "D1") (pin "2") (pinfunction "GND_2") (pintype "bidirectional"))
      (node (ref "D10") (pin "2") (pinfunction "2_2") (pintype "passive"))
      (node (ref "D11") (pin "2") (pinfunction "2_2") (pintype "passive"))
      (node (ref "D12") (pin "2") (pinfunction "2_2") (pintype "passive"))
      (node (ref "D3") (pin "2") (pinfunction "K_2") (pintype "bidirectional"))
      (node (ref "D6") (pin "2") (pinfunction "2_2") (pintype "passive"))
      (node (ref "D8") (pin "2") (pinfunction "2_2") (pintype "passive"))
      (node (ref "D9") (pin "2") (pinfunction "2_2") (pintype "passive"))
      (node (ref "EPD_C1") (pin "2") (pinfunction "2_2") (pintype "passive"))
      (node (ref "EPD_C10") (pin "2") (pinfunction "2_2") (pintype "passive"))
      (node (ref "EPD_C11") (pin "2") (pinfunction "2_2") (pintype "passive"))
      (node (ref "EPD_C12") (pin "2") (pinfunction "2_2") (pintype "passive"))
      (node (ref "EPD_C2") (pin "2") (pinfunction "2_2") (pintype "passive"))
      (node (ref "EPD_C5") (pin "2") (pinfunction "2_2") (pintype "passive"))
      (node (ref "EPD_C6") (pin "2") (pinfunction "2_2") (pintype "passive"))
      (node (ref "EPD_C7") (pin "2") (pinfunction "2_2") (pintype "passive"))
      (node (ref "EPD_C8") (pin "2") (pinfunction "2_2") (pintype "passive"))
      (node (ref "EPD_C9") (pin "2") (pinfunction "2_2") (pintype "passive"))
      (node (ref "IC1") (pin "3") (pinfunction "GND_3") (pintype "bidirectional"))
      (node (ref "IC4") (pin "2") (pinfunction "VSS_2") (pintype "bidirectional"))
      (node (ref "J1") (pin "17") (pinfunction "17_17") (pintype "bidirectional"))
      (node (ref "J1") (pin "8") (pinfunction "8_8") (pintype "bidirectional"))
      (node (ref "J1") (pin "MP1") (pinfunction "MP1_MP1") (pintype "bidirectional"))
      (node (ref "J1") (pin "MP2") (pinfunction "MP2_MP2") (pintype "bidirectional"))
      (node (ref "J2") (pin "A1") (pinfunction "A1_A1") (pintype "bidirectional"))
      (node (ref "J2") (pin "A12") (pinfunction "A12_A12") (pintype "bidirectional"))
      (node (ref "J2") (pin "B1") (pinfunction "B1_B1") (pintype "bidirectional"))
      (node (ref "J2") (pin "B12") (pinfunction "B12_B12") (pintype "bidirectional"))
      (node (ref "J2") (pin "MP1") (pinfunction "MP1_MP1") (pintype "bidirectional"))
      (node (ref "J2") (pin "MP2") (pinfunction "MP2_MP2") (pintype "bidirectional"))
      (node (ref "J2") (pin "MP3") (pinfunction "MP3_MP3") (pintype "bidirectional"))
      (node (ref "J2") (pin "MP4") (pinfunction "MP4_MP4") (pintype "bidirectional"))
      (node (ref "J3") (pin "1") (pinfunction "1_1") (pintype "power_in"))
      (node (ref "J4") (pin "G1") (pinfunction "GND_1_G1") (pintype "bidirectional"))
      (node (ref "J4") (pin "G2") (pinfunction "GND_2_G2") (pintype "bidirectional"))
      (node (ref "J4") (pin "G3") (pinfunction "GND_3_G3") (pintype "bidirectional"))
      (node (ref "J4") (pin "G4") (pinfunction "GND_4_G4") (pintype "bidirectional"))
      (node (ref "J4") (pin "P6") (pinfunction "VSS_P6") (pintype "bidirectional"))
      (node (ref "R1_PWRUSB") (pin "1") (pinfunction "1_1") (pintype "passive"))
      (node (ref "R2") (pin "1") (pinfunction "1_1") (pintype "passive"))
      (node (ref "R2-USB") (pin "2") (pinfunction "2_2") (pintype "passive"))
      (node (ref "R2-USB1") (pin "1") (pinfunction "1_1") (pintype "passive"))
      (node (ref "R2_BAT") (pin "1") (pinfunction "1_1") (pintype "passive"))
      (node (ref "R4") (pin "2") (pinfunction "2_2") (pintype "passive"))
      (node (ref "RESET_BUTTON") (pin "1") (pinfunction "1_1") (pintype "passive"))
      (node (ref "RESET_BUTTON") (pin "2") (pinfunction "2_2") (pintype "passive"))
      (node (ref "SENSOR2") (pin "1") (pinfunction "GND_1") (pintype "power_in"))
      (node (ref "SENSOR2") (pin "5") (pinfunction "SDO_5") (pintype "bidirectional"))
      (node (ref "SENSOR2") (pin "7") (pinfunction "GND_7") (pintype "power_in"))
      (node (ref "SJ1") (pin "1") (pinfunction "1_1") (pintype "passive"))
      (node (ref "TP4") (pin "TP") (pinfunction "TP_TP") (pintype "input"))
      (node (ref "TP5") (pin "TP") (pinfunction "TP_TP") (pintype "input"))
      (node (ref "U1") (pin "4") (pinfunction "GND_4") (pintype "power_in"))
      (node (ref "U1") (pin "9") (pinfunction "EXP_9") (pintype "passive"))
      (node (ref "U2") (pin "1") (pinfunction "GND_1") (pintype "power_in"))
      (node (ref "U2") (pin "28") (pinfunction "GND_28") (pintype "power_in"))
      (node (ref "U2") (pin "29_1") (pinfunction "GND_29_1") (pintype "power_in"))
      (node (ref "U2") (pin "29_2") (pinfunction "GND_29_2") (pintype "power_in"))
      (node (ref "U2") (pin "29_3") (pinfunction "GND_29_3") (pintype "power_in"))
      (node (ref "U2") (pin "29_4") (pinfunction "GND_29_4") (pintype "power_in"))
      (node (ref "U2") (pin "29_5") (pinfunction "GND_29_5") (pintype "power_in"))
      (node (ref "U2") (pin "29_6") (pinfunction "GND_29_6") (pintype "power_in"))
      (node (ref "U2") (pin "29_7") (pinfunction "GND_29_7") (pintype "power_in"))
      (node (ref "U2") (pin "29_8") (pinfunction "GND_29_8") (pintype "power_in"))
      (node (ref "U2") (pin "29_9") (pinfunction "GND_29_9") (pintype "power_in"))
      (node (ref "U3") (pin "13") (pinfunction "GND_13") (pintype "power_in"))
      (node (ref "U4") (pin "1") (pinfunction "CTG_1") (pintype "power_in"))
      (node (ref "U4") (pin "4") (pinfunction "GND_4") (pintype "power_in"))
      (node (ref "U4") (pin "6") (pinfunction "QSTRT_6") (pintype "input"))
      (node (ref "U4") (pin "9") (pinfunction "EP_9") (pintype "power_in"))
      (node (ref "U5") (pin "2") (pinfunction "VSS_2") (pintype "power_in"))
    )
    (net (code "14") (name "GPIO8") (class "Default")
      (node (ref "R1") (pin "2") (pinfunction "2_2") (pintype "passive"))
      (node (ref "U2") (pin "10") (pinfunction "IO8_10") (pintype "bidirectional"))
    )
    (net (code "15") (name "I2C_PW") (class "Default")
      (node (ref "C1") (pin "1") (pinfunction "1_1") (pintype "passive"))
      (node (ref "C2") (pin "1") (pinfunction "1_1") (pintype "passive"))
      (node (ref "R1-PINH") (pin "2") (pinfunction "2_2") (pintype "passive"))
      (node (ref "R2-PINH") (pin "2") (pinfunction "2_2") (pintype "passive"))
      (node (ref "SENSOR2") (pin "2") (pinfunction "CSB_2") (pintype "input"))
      (node (ref "SENSOR2") (pin "6") (pinfunction "VDDIO_6") (pintype "power_in"))
      (node (ref "SENSOR2") (pin "8") (pinfunction "VDD_8") (pintype "power_in"))
      (node (ref "U2") (pin "17") (pinfunction "IO19_17") (pintype "bidirectional"))
    )
    (net (code "16") (name "INT_RTC") (class "Default")
      (node (ref "R1-PINH1") (pin "1") (pinfunction "1_1") (pintype "passive"))
      (node (ref "TP15") (pin "TP") (pinfunction "TP_TP") (pintype "input"))
      (node (ref "U2") (pin "8") (pinfunction "IO0_8") (pintype "bidirectional"))
      (node (ref "U3") (pin "3") (pinfunction "SQW/~{INT}_3") (pintype "output"))
    )
    (net (code "17") (name "IO{slash}BOOT") (class "Default")
      (node (ref "BOOT_BUTTON") (pin "3") (pinfunction "3_3") (pintype "passive"))
      (node (ref "BOOT_BUTTON") (pin "4") (pinfunction "4_4") (pintype "passive"))
      (node (ref "C6") (pin "1") (pinfunction "1_1") (pintype "passive"))
      (node (ref "R_BOOT") (pin "2") (pinfunction "2_2") (pintype "passive"))
      (node (ref "U2") (pin "15") (pinfunction "IO9_15") (pintype "bidirectional"))
    )
    (net (code "18") (name "IO{slash}CHANGE") (class "Default")
      (node (ref "C10") (pin "1") (pinfunction "1_1") (pintype "passive"))
      (node (ref "CHANGE_BUTTON") (pin "3") (pinfunction "3_3") (pintype "passive"))
      (node (ref "CHANGE_BUTTON") (pin "4") (pinfunction "4_4") (pintype "passive"))
      (node (ref "R_CHANGE") (pin "2") (pinfunction "2_2") (pintype "passive"))
      (node (ref "U2") (pin "23") (pinfunction "IO15_23") (pintype "bidirectional"))
    )
    (net (code "19") (name "MISO") (class "Default")
      (node (ref "D12") (pin "1") (pinfunction "1_1") (pintype "passive"))
      (node (ref "J4") (pin "P7") (pinfunction "DAT0_P7") (pintype "bidirectional"))
      (node (ref "R8") (pin "1") (pinfunction "1_1") (pintype "passive"))
      (node (ref "TP6") (pin "TP") (pinfunction "TP_TP") (pintype "input"))
      (node (ref "U1") (pin "2") (pinfunction "DO(IO1)_2") (pintype "bidirectional"))
      (node (ref "U2") (pin "27") (pinfunction "IO2_27") (pintype "bidirectional"))
    )
    (net (code "20") (name "MOSI") (class "Default")
      (node (ref "D11") (pin "1") (pinfunction "1_1") (pintype "passive"))
      (node (ref "J1") (pin "14") (pinfunction "14_14") (pintype "bidirectional"))
      (node (ref "J4") (pin "P3") (pinfunction "CMD_P3") (pintype "bidirectional"))
      (node (ref "R7") (pin "1") (pinfunction "1_1") (pintype "passive"))
      (node (ref "TP7") (pin "TP") (pinfunction "TP_TP") (pintype "input"))
      (node (ref "U1") (pin "5") (pinfunction "DI(IO0)_5") (pintype "bidirectional"))
      (node (ref "U2") (pin "7") (pinfunction "IO7_7") (pintype "bidirectional"))
    )
    (net (code "21") (name "Net-(CHG_LED-PadC)") (class "Default")
      (node (ref "CHG_LED") (pin "C") (pinfunction "C_C") (pintype "passive"))
      (node (ref "R1_BAT") (pin "2") (pinfunction "2_2") (pintype "passive"))
    )
    (net (code "22") (name "Net-(D2-CATHODE)") (class "Default")
      (node (ref "C1_BAT1") (pin "1") (pinfunction "1_1") (pintype "passive"))
      (node (ref "D2") (pin "2") (pinfunction "CATHODE_2") (pintype "bidirectional"))
      (node (ref "IC4") (pin "1") (pinfunction "VIN_1") (pintype "bidirectional"))
      (node (ref "IC4") (pin "3") (pinfunction "CE_3") (pintype "bidirectional"))
      (node (ref "Q1") (pin "3") (pinfunction "S_3") (pintype "bidirectional"))
    )
    (net (code "23") (name "Net-(D3-A)") (class "Default")
      (node (ref "C4") (pin "1") (pinfunction "1_1") (pintype "passive"))
      (node (ref "D3") (pin "1") (pinfunction "A_1") (pintype "bidirectional"))
      (node (ref "D4") (pin "2") (pinfunction "K_2") (pintype "bidirectional"))
    )
    (net (code "24") (name "Net-(D7-CATHODE)") (class "Default")
      (node (ref "D7") (pin "2") (pinfunction "CATHODE_2") (pintype "bidirectional"))
      (node (ref "R_CAPACITOR") (pin "2") (pinfunction "2_2") (pintype "passive"))
    )
    (net (code "25") (name "Net-(EPD_C1-Pad1)") (class "Default")
      (node (ref "EPD_C1") (pin "1") (pinfunction "1_1") (pintype "passive"))
      (node (ref "J1") (pin "4") (pinfunction "4_4") (pintype "bidirectional"))
    )
    (net (code "26") (name "Net-(EPD_C2-Pad1)") (class "Default")
      (node (ref "EPD_C2") (pin "1") (pinfunction "1_1") (pintype "passive"))
      (node (ref "J1") (pin "5") (pinfunction "5_5") (pintype "bidirectional"))
    )
    (net (code "27") (name "Net-(EPD_C6-Pad1)") (class "Default")
      (node (ref "EPD_C6") (pin "1") (pinfunction "1_1") (pintype "passive"))
      (node (ref "J1") (pin "18") (pinfunction "18_18") (pintype "bidirectional"))
    )
    (net (code "28") (name "Net-(EPD_C7-Pad1)") (class "Default")
      (node (ref "EPD_C7") (pin "1") (pinfunction "1_1") (pintype "passive"))
      (node (ref "J1") (pin "19") (pinfunction "19_19") (pintype "bidirectional"))
    )
    (net (code "29") (name "Net-(EPD_C8-Pad1)") (class "Default")
      (node (ref "EPD_C8") (pin "1") (pinfunction "1_1") (pintype "passive"))
      (node (ref "J1") (pin "20") (pinfunction "20_20") (pintype "bidirectional"))
    )
    (net (code "30") (name "Net-(EPD_C10-Pad1)") (class "Default")
      (node (ref "EPD_C10") (pin "1") (pinfunction "1_1") (pintype "passive"))
      (node (ref "J1") (pin "22") (pinfunction "22_22") (pintype "bidirectional"))
    )
    (net (code "31") (name "Net-(EPD_C12-Pad1)") (class "Default")
      (node (ref "EPD_C12") (pin "1") (pinfunction "1_1") (pintype "passive"))
      (node (ref "J1") (pin "24") (pinfunction "24_24") (pintype "bidirectional"))
    )
    (net (code "32") (name "Net-(IC1-CT)") (class "Default")
      (node (ref "C_DELAY") (pin "1") (pinfunction "1_1") (pintype "passive"))
      (node (ref "IC1") (pin "5") (pinfunction "CT_5") (pintype "bidirectional"))
    )
    (net (code "33") (name "Net-(J2-PadA5)") (class "Default")
      (node (ref "J2") (pin "A5") (pinfunction "A5_A5") (pintype "bidirectional"))
      (node (ref "R2-USB1") (pin "2") (pinfunction "2_2") (pintype "passive"))
    )
    (net (code "34") (name "Net-(J2-PadB5)") (class "Default")
      (node (ref "J2") (pin "B5") (pinfunction "B5_B5") (pintype "bidirectional"))
      (node (ref "R2-USB") (pin "1") (pinfunction "1_1") (pintype "passive"))
    )
    (net (code "35") (name "Net-(U5-PROG)") (class "Default")
      (node (ref "R2_BAT") (pin "2") (pinfunction "2_2") (pintype "passive"))
      (node (ref "U5") (pin "5") (pinfunction "PROG_5") (pintype "input"))
    )
    (net (code "36") (name "Net-(U5-STAT)") (class "Default")
      (node (ref "R1_BAT") (pin "1") (pinfunction "1_1") (pintype "passive"))
      (node (ref "U5") (pin "1") (pinfunction "STAT_1") (pintype "output"))
    )
    (net (code "37") (name "PREVGH") (class "Default")
      (node (ref "D5") (pin "2") (pinfunction "K_2") (pintype "bidirectional"))
      (node (ref "EPD_C9") (pin "1") (pinfunction "1_1") (pintype "passive"))
      (node (ref "J1") (pin "21") (pinfunction "21_21") (pintype "bidirectional"))
    )
    (net (code "38") (name "PREVGL") (class "Default")
      (node (ref "D4") (pin "1") (pinfunction "A_1") (pintype "bidirectional"))
      (node (ref "EPD_C11") (pin "1") (pinfunction "1_1") (pintype "passive"))
      (node (ref "J1") (pin "23") (pinfunction "23_23") (pintype "bidirectional"))
    )
    (net (code "39") (name "RESE") (class "Default")
      (node (ref "J1") (pin "3") (pinfunction "3_3") (pintype "bidirectional"))
      (node (ref "Q3") (pin "2") (pinfunction "S_2") (pintype "bidirectional"))
      (node (ref "R3") (pin "1") (pinfunction "1_1") (pintype "passive"))
    )
    (net (code "40") (name "RESE'") (class "Default")
      (node (ref "R2") (pin "2") (pinfunction "2_2") (pintype "passive"))
      (node (ref "R3") (pin "2") (pinfunction "2_2") (pintype "passive"))
      (node (ref "SJ1") (pin "2") (pinfunction "2_2") (pintype "passive"))
    )
    (net (code "41") (name "RESET") (class "Default")
      (node (ref "C5") (pin "1") (pinfunction "1_1") (pintype "passive"))
      (node (ref "IC1") (pin "1") (pinfunction "VOUT_1") (pintype "bidirectional"))
      (node (ref "RESET_BUTTON") (pin "3") (pinfunction "3_3") (pintype "passive"))
      (node (ref "RESET_BUTTON") (pin "4") (pinfunction "4_4") (pintype "passive"))
      (node (ref "R_RESET") (pin "2") (pinfunction "2_2") (pintype "passive"))
      (node (ref "U2") (pin "3") (pinfunction "EN_3") (pintype "input"))
    )
    (net (code "42") (name "RTC_RST") (class "Default")
      (node (ref "U2") (pin "16") (pinfunction "IO18_16") (pintype "bidirectional"))
      (node (ref "U3") (pin "4") (pinfunction "~{RST}_4") (pintype "input"))
    )
    (net (code "43") (name "RX") (class "Default")
      (node (ref "TP2") (pin "TP") (pinfunction "TP_TP") (pintype "input"))
      (node (ref "U2") (pin "24") (pinfunction "RXD0/GPIO17_24") (pintype "bidirectional"))
    )
    (net (code "44") (name "SCK") (class "Default")
      (node (ref "D10") (pin "1") (pinfunction "1_1") (pintype "passive"))
      (node (ref "J1") (pin "13") (pinfunction "13_13") (pintype "bidirectional"))
      (node (ref "J4") (pin "P5") (pinfunction "CLK_P5") (pintype "bidirectional"))
      (node (ref "R6") (pin "1") (pinfunction "1_1") (pintype "passive"))
      (node (ref "TP8") (pin "TP") (pinfunction "TP_TP") (pintype "input"))
      (node (ref "U1") (pin "6") (pinfunction "CLK_6") (pintype "input"))
      (node (ref "U2") (pin "6") (pinfunction "IO6_6") (pintype "bidirectional"))
    )
    (net (code "45") (name "SCL") (class "Default")
      (node (ref "J3") (pin "4") (pinfunction "4_4") (pintype "passive"))
      (node (ref "R2-PINH") (pin "1") (pinfunction "1_1") (pintype "passive"))
      (node (ref "SENSOR2") (pin "4") (pinfunction "SCK_4") (pintype "input"))
      (node (ref "U2") (pin "20") (pinfunction "IO22_20") (pintype "bidirectional"))
      (node (ref "U3") (pin "16") (pinfunction "SCL_16") (pintype "input"))
      (node (ref "U4") (pin "7") (pinfunction "SCL_7") (pintype "input"))
    )
    (net (code "46") (name "SDA") (class "Default")
      (node (ref "J3") (pin "3") (pinfunction "3_3") (pintype "passive"))
      (node (ref "R1-PINH") (pin "1") (pinfunction "1_1") (pintype "passive"))
      (node (ref "SENSOR2") (pin "3") (pinfunction "SDI_3") (pintype "bidirectional"))
      (node (ref "U2") (pin "19") (pinfunction "IO21_19") (pintype "bidirectional"))
      (node (ref "U3") (pin "15") (pinfunction "SDA_15") (pintype "bidirectional"))
      (node (ref "U4") (pin "8") (pinfunction "SDA_8") (pintype "bidirectional"))
    )
    (net (code "47") (name "SRC") (class "Default")
      (node (ref "C4") (pin "2") (pinfunction "2_2") (pintype "passive"))
      (node (ref "D5") (pin "1") (pinfunction "A_1") (pintype "bidirectional"))
      (node (ref "L1") (pin "1") (pinfunction "1_1") (pintype "passive"))
      (node (ref "Q3") (pin "3") (pinfunction "D_3") (pintype "bidirectional"))
    )
    (net (code "48") (name "SS_SD") (class "Default")
      (node (ref "D8") (pin "1") (pinfunction "1_1") (pintype "passive"))
      (node (ref "J4") (pin "P2") (pinfunction "CD/DAT3_P2") (pintype "bidirectional"))
      (node (ref "R10") (pin "1") (pinfunction "1_1") (pintype "passive"))
      (node (ref "U2") (pin "4") (pinfunction "IO4_4") (pintype "bidirectional"))
    )
    (net (code "49") (name "TX") (class "Default")
      (node (ref "TP1") (pin "TP") (pinfunction "TP_TP") (pintype "input"))
      (node (ref "U2") (pin "25") (pinfunction "TXD0/GPIO16_25") (pintype "bidirectional"))
    )
    (net (code "50") (name "USB_D+") (class "Default")
      (node (ref "D1") (pin "1") (pinfunction "I/O1_1_1") (pintype "bidirectional"))
      (node (ref "U2") (pin "14") (pinfunction "IO13_14") (pintype "bidirectional"))
    )
    (net (code "51") (name "USB_D-") (class "Default")
      (node (ref "D1") (pin "3") (pinfunction "I/O2_1_3") (pintype "bidirectional"))
      (node (ref "U2") (pin "13") (pinfunction "IO12_13") (pintype "bidirectional"))
    )
    (net (code "52") (name "VBAT") (class "Default")
      (node (ref "C2_BAT") (pin "1") (pinfunction "1_1") (pintype "passive"))
      (node (ref "Q1") (pin "1") (pinfunction "D_1") (pintype "bidirectional"))
      (node (ref "TP3") (pin "TP") (pinfunction "TP_TP") (pintype "input"))
      (node (ref "U4") (pin "2") (pinfunction "CELL_2") (pintype "power_in"))
      (node (ref "U4") (pin "3") (pinfunction "VDD_3") (pintype "power_in"))
      (node (ref "U5") (pin "3") (pinfunction "VBAT_3") (pintype "power_in"))
    )
    (net (code "53") (name "VBUS") (class "Default")
      (node (ref "C1_BAT") (pin "1") (pinfunction "1_1") (pintype "passive"))
      (node (ref "C4_USB") (pin "1") (pinfunction "1_1") (pintype "passive"))
      (node (ref "C5_USB") (pin "1") (pinfunction "1_1") (pintype "passive"))
      (node (ref "CHG_LED") (pin "A") (pinfunction "A_A") (pintype "passive"))
      (node (ref "D1") (pin "5") (pinfunction "VBUS_5") (pintype "bidirectional"))
      (node (ref "D2") (pin "1") (pinfunction "ANODE_1") (pintype "bidirectional"))
      (node (ref "Q1") (pin "2") (pinfunction "G_2") (pintype "bidirectional"))
      (node (ref "R1_PWRUSB") (pin "2") (pinfunction "2_2") (pintype "passive"))
      (node (ref "TP14") (pin "TP") (pinfunction "TP_TP") (pintype "input"))
      (node (ref "U5") (pin "4") (pinfunction "VIN_4") (pintype "power_in"))
    )
    (net (code "54") (name "VRTC") (class "Default")
      (node (ref "C10_SUPERCAP") (pin "2") (pinfunction "2_2") (pintype "passive"))
      (node (ref "C8") (pin "1") (pinfunction "1_1") (pintype "passive"))
      (node (ref "R_CAPACITOR") (pin "1") (pinfunction "1_1") (pintype "passive"))
      (node (ref "U3") (pin "14") (pinfunction "VBAT_14") (pintype "power_in"))
    )
    (net (code "55") (name "VUSB") (class "Default")
      (node (ref "J2") (pin "A4") (pinfunction "A4_A4") (pintype "bidirectional"))
      (node (ref "J2") (pin "A9") (pinfunction "A9_A9") (pintype "bidirectional"))
      (node (ref "J2") (pin "B4") (pinfunction "B4_B4") (pintype "bidirectional"))
      (node (ref "J2") (pin "B9") (pinfunction "B9_B9") (pintype "bidirectional"))
      (node (ref "PFMF.050.1") (pin "1") (pinfunction "1_1") (pintype "passive"))
      (node (ref "PFMF.050.1") (pin "2") (pinfunction "2_2") (pintype "passive"))
    )
    (net (code "56") (name "unconnected-(IC1-NC-Pad4)") (class "Default")
      (node (ref "IC1") (pin "4") (pinfunction "NC_4") (pintype "no_connect"))
    )
    (net (code "57") (name "unconnected-(IC4-NC-Pad4)") (class "Default")
      (node (ref "IC4") (pin "4") (pinfunction "NC_4") (pintype "no_connect"))
    )
    (net (code "58") (name "unconnected-(J1-Pad1)") (class "Default")
      (node (ref "J1") (pin "1") (pinfunction "1_1") (pintype "bidirectional"))
    )
    (net (code "59") (name "unconnected-(J1-Pad6)") (class "Default")
      (node (ref "J1") (pin "6") (pinfunction "6_6") (pintype "bidirectional"))
    )
    (net (code "60") (name "unconnected-(J1-Pad7)") (class "Default")
      (node (ref "J1") (pin "7") (pinfunction "7_7") (pintype "bidirectional"))
    )
    (net (code "61") (name "unconnected-(J2-PadA8)") (class "Default")
      (node (ref "J2") (pin "A8") (pinfunction "A8_A8") (pintype "bidirectional"))
    )
    (net (code "62") (name "unconnected-(J2-PadB8)") (class "Default")
      (node (ref "J2") (pin "B8") (pinfunction "B8_B8") (pintype "bidirectional"))
    )
    (net (code "63") (name "unconnected-(J4-DAT1-PadP8)") (class "Default")
      (node (ref "J4") (pin "P8") (pinfunction "DAT1_P8") (pintype "bidirectional"))
    )
    (net (code "64") (name "unconnected-(J4-DAT2-PadP1)") (class "Default")
      (node (ref "J4") (pin "P1") (pinfunction "DAT2_P1") (pintype "bidirectional"))
    )
    (net (code "65") (name "unconnected-(J4-DETECTION_1-PadS1)") (class "Default")
      (node (ref "J4") (pin "S1") (pinfunction "DETECTION_1_S1") (pintype "bidirectional"))
    )
    (net (code "66") (name "unconnected-(J4-DETECTION_2-PadS2)") (class "Default")
      (node (ref "J4") (pin "S2") (pinfunction "DETECTION_2_S2") (pintype "bidirectional"))
    )
    (net (code "67") (name "unconnected-(U2-NC-Pad22)") (class "Default")
      (node (ref "U2") (pin "22") (pinfunction "NC_22") (pintype "no_connect"))
    )
    (net (code "68") (name "unconnected-(U4-~{ALERT}-Pad5)") (class "Default")
      (node (ref "U4") (pin "5") (pinfunction "~{ALERT}_5") (pintype "output"))
    )
  )
)
